# B171X.net
KiCad netlist of a schematic drawn in EAGLE
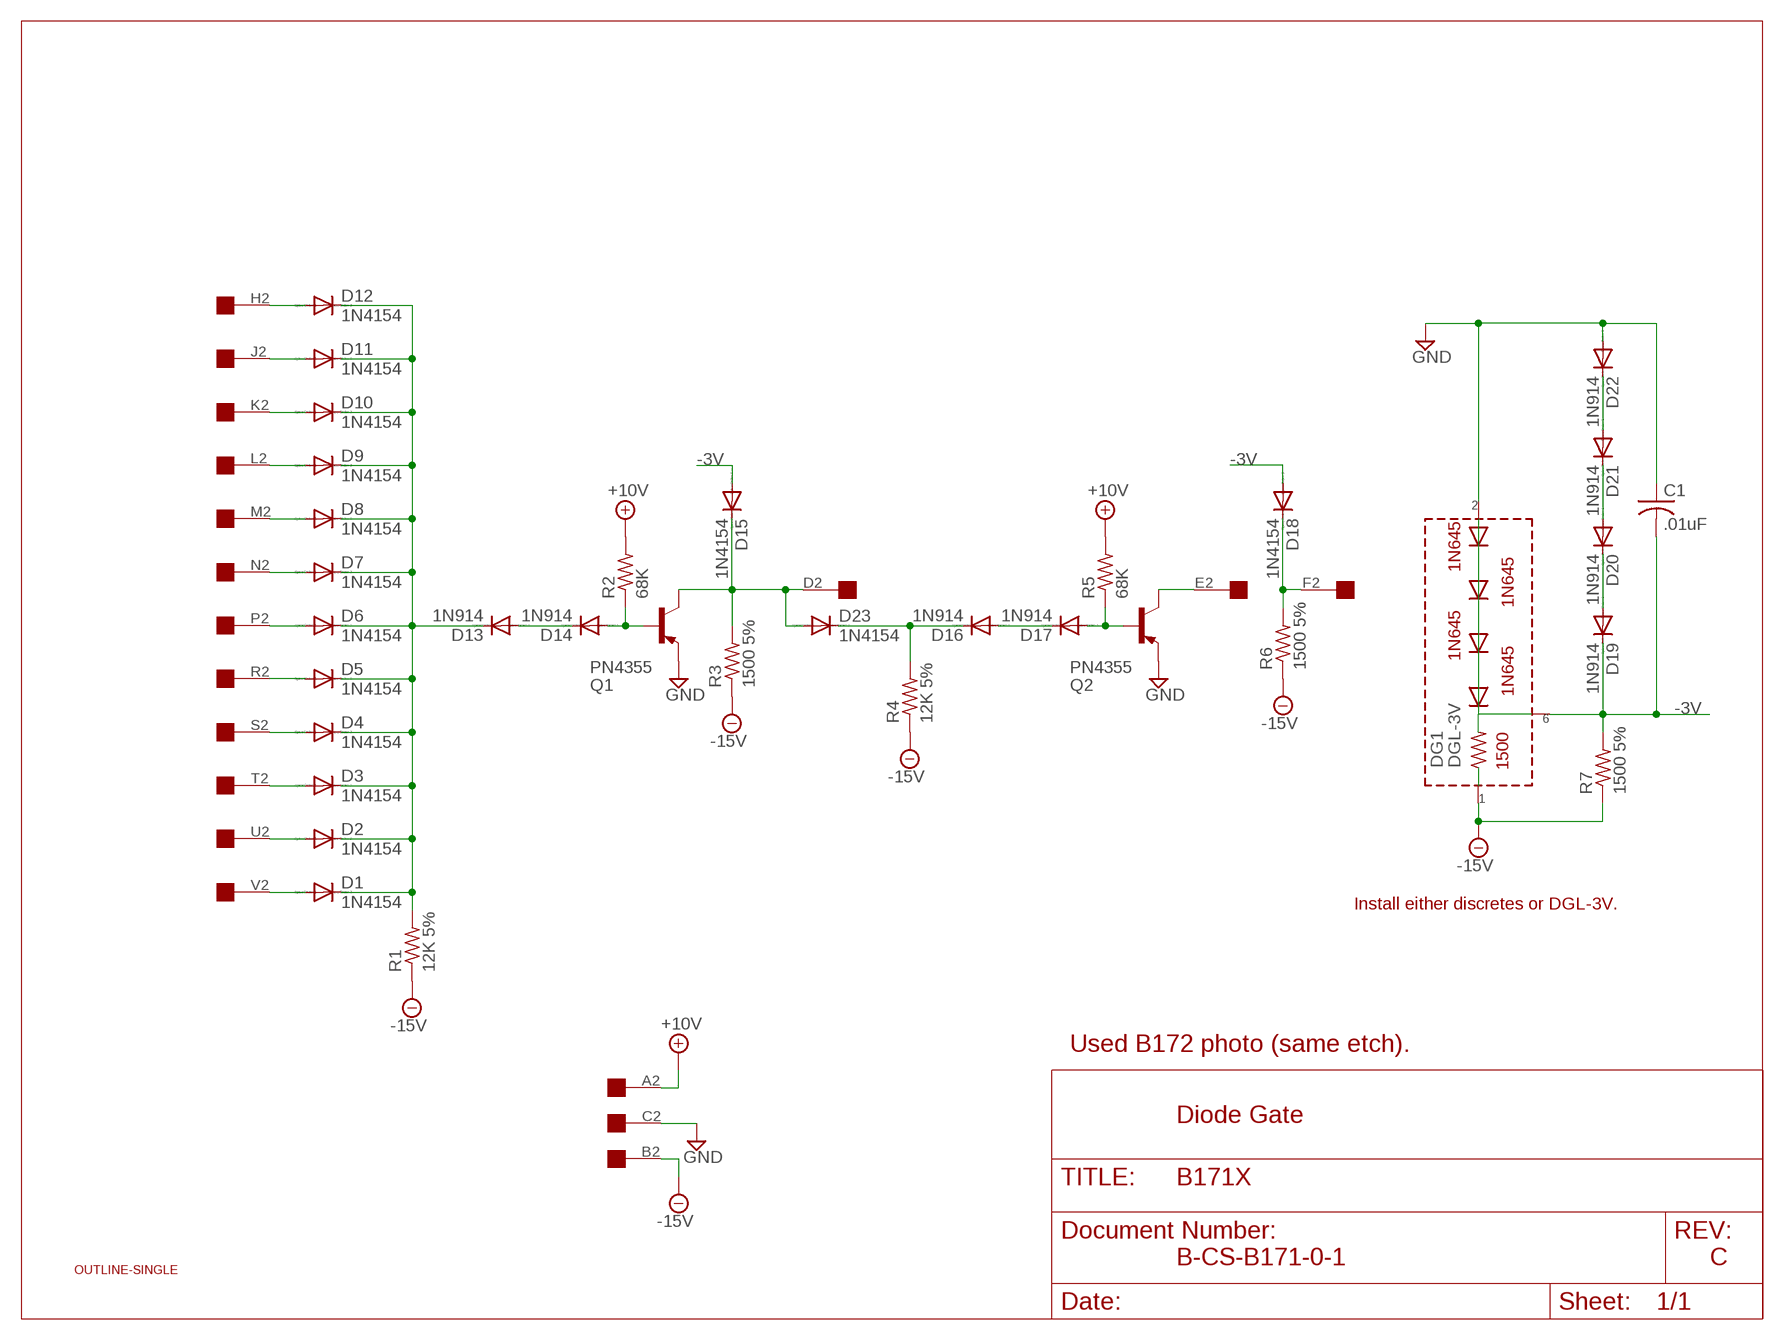
[diagram p0: schematic, sheet 1]

(export (version "E")
  (design (tool "Eeschema 10.0.6"))
  (components
    (comp (ref "C1")
      (value ".01uF")
      (footprint "eagle-import:C050-025X075")
      (libsource (lib "eagle-import") (part "C-US050-025X075"))
    )
    (comp (ref "D1")
      (value "1N4154")
      (footprint "eagle-import:DO35-10")
      (libsource (lib "eagle-import") (part "DIODE-DO35-10"))
    )
    (comp (ref "D2")
      (value "1N4154")
      (footprint "eagle-import:DO35-10")
      (libsource (lib "eagle-import") (part "DIODE-DO35-10"))
    )
    (comp (ref "D3")
      (value "1N4154")
      (footprint "eagle-import:DO35-10")
      (libsource (lib "eagle-import") (part "DIODE-DO35-10"))
    )
    (comp (ref "D4")
      (value "1N4154")
      (footprint "eagle-import:DO35-10")
      (libsource (lib "eagle-import") (part "DIODE-DO35-10"))
    )
    (comp (ref "D5")
      (value "1N4154")
      (footprint "eagle-import:DO35-10")
      (libsource (lib "eagle-import") (part "DIODE-DO35-10"))
    )
    (comp (ref "D6")
      (value "1N4154")
      (footprint "eagle-import:DO35-10")
      (libsource (lib "eagle-import") (part "DIODE-DO35-10"))
    )
    (comp (ref "D7")
      (value "1N4154")
      (footprint "eagle-import:DO35-10")
      (libsource (lib "eagle-import") (part "DIODE-DO35-10"))
    )
    (comp (ref "D8")
      (value "1N4154")
      (footprint "eagle-import:DO35-10")
      (libsource (lib "eagle-import") (part "DIODE-DO35-10"))
    )
    (comp (ref "D9")
      (value "1N4154")
      (footprint "eagle-import:DO35-10")
      (libsource (lib "eagle-import") (part "DIODE-DO35-10"))
    )
    (comp (ref "D10")
      (value "1N4154")
      (footprint "eagle-import:DO35-10")
      (libsource (lib "eagle-import") (part "DIODE-DO35-10"))
    )
    (comp (ref "D11")
      (value "1N4154")
      (footprint "eagle-import:DO35-10")
      (libsource (lib "eagle-import") (part "DIODE-DO35-10"))
    )
    (comp (ref "D12")
      (value "1N4154")
      (footprint "eagle-import:DO35-10")
      (libsource (lib "eagle-import") (part "DIODE-DO35-10"))
    )
    (comp (ref "D13")
      (value "1N914")
      (footprint "eagle-import:DO35-10")
      (libsource (lib "eagle-import") (part "DIODE-DO35-10"))
    )
    (comp (ref "D14")
      (value "1N914")
      (footprint "eagle-import:DO35-10")
      (libsource (lib "eagle-import") (part "DIODE-DO35-10"))
    )
    (comp (ref "D15")
      (value "1N4154")
      (footprint "eagle-import:DO35-10")
      (libsource (lib "eagle-import") (part "DIODE-DO35-10"))
    )
    (comp (ref "D16")
      (value "1N914")
      (footprint "eagle-import:DO35-10")
      (libsource (lib "eagle-import") (part "DIODE-DO35-10"))
    )
    (comp (ref "D17")
      (value "1N914")
      (footprint "eagle-import:DO35-10")
      (libsource (lib "eagle-import") (part "DIODE-DO35-10"))
    )
    (comp (ref "D18")
      (value "1N4154")
      (footprint "eagle-import:DO35-10")
      (libsource (lib "eagle-import") (part "DIODE-DO35-10"))
    )
    (comp (ref "D19")
      (value "1N914")
      (footprint "eagle-import:DO35-10")
      (libsource (lib "eagle-import") (part "DIODE-DO35-10"))
    )
    (comp (ref "D20")
      (value "1N914")
      (footprint "eagle-import:DO35-10")
      (libsource (lib "eagle-import") (part "DIODE-DO35-10"))
    )
    (comp (ref "D21")
      (value "1N914")
      (footprint "eagle-import:DO35-10")
      (libsource (lib "eagle-import") (part "DIODE-DO35-10"))
    )
    (comp (ref "D22")
      (value "1N914")
      (footprint "eagle-import:DO35-10")
      (libsource (lib "eagle-import") (part "DIODE-DO35-10"))
    )
    (comp (ref "D23")
      (value "1N4154")
      (footprint "eagle-import:DO35-10")
      (libsource (lib "eagle-import") (part "DIODE-DO35-10"))
    )
    (comp (ref "DG1")
      (value "DGL-3V")
      (footprint "eagle-import:DGL2")
      (libsource (lib "eagle-import") (part "DGL-3V"))
    )
    (comp (ref "Q1")
      (value "PN4355")
      (footprint "eagle-import:TO5")
      (libsource (lib "eagle-import") (part "-PNP-TO5"))
    )
    (comp (ref "Q2")
      (value "PN4355")
      (footprint "eagle-import:TO5")
      (libsource (lib "eagle-import") (part "-PNP-TO5"))
    )
    (comp (ref "R1")
      (value "12K 5%")
      (footprint "eagle-import:0207_10")
      (libsource (lib "eagle-import") (part "R-US_0207/10"))
    )
    (comp (ref "R2")
      (value "68K")
      (footprint "eagle-import:0207_10")
      (libsource (lib "eagle-import") (part "R-US_0207/10"))
    )
    (comp (ref "R3")
      (value "1500 5%")
      (footprint "eagle-import:0207_10")
      (libsource (lib "eagle-import") (part "R-US_0207/10"))
    )
    (comp (ref "R4")
      (value "12K 5%")
      (footprint "eagle-import:0207_10")
      (libsource (lib "eagle-import") (part "R-US_0207/10"))
    )
    (comp (ref "R5")
      (value "68K")
      (footprint "eagle-import:0207_10")
      (libsource (lib "eagle-import") (part "R-US_0207/10"))
    )
    (comp (ref "R6")
      (value "1500 5%")
      (footprint "eagle-import:0207_10")
      (libsource (lib "eagle-import") (part "R-US_0207/10"))
    )
    (comp (ref "R7")
      (value "1500 5%")
      (footprint "eagle-import:0207_10")
      (libsource (lib "eagle-import") (part "R-US_0207/10"))
    )
    (comp (ref "U$1")
      (value "OUTLINE-SINGLE")
      (footprint "eagle-import:SINGLE")
      (libsource (lib "eagle-import") (part "OUTLINE-SINGLE"))
    )
    (comp (ref "U$2")
      (value "EDGE-1")
      (footprint "eagle-import:EDGE-CON1")
      (libsource (lib "eagle-import") (part "EDGE-1"))
    )
  )
  (nets
    (net (code "1") (name "+10V") (class "Default")
      (node (ref "R2") (pin "2") (pinfunction "2_2") (pintype "passive"))
      (node (ref "R5") (pin "2") (pinfunction "2_2") (pintype "passive"))
      (node (ref "U$2") (pin "A2") (pinfunction "1_A2") (pintype "bidirectional"))
    )
    (net (code "2") (name "-15V") (class "Default")
      (node (ref "DG1") (pin "P$1") (pinfunction "1_P$1") (pintype "passive"))
      (node (ref "R1") (pin "1") (pinfunction "1_1") (pintype "passive"))
      (node (ref "R3") (pin "1") (pinfunction "1_1") (pintype "passive"))
      (node (ref "R4") (pin "1") (pinfunction "1_1") (pintype "passive"))
      (node (ref "R6") (pin "1") (pinfunction "1_1") (pintype "passive"))
      (node (ref "R7") (pin "1") (pinfunction "1_1") (pintype "passive"))
      (node (ref "U$2") (pin "B2") (pinfunction "1_B2") (pintype "bidirectional"))
    )
    (net (code "3") (name "/-3V") (class "Default")
      (node (ref "C1") (pin "2") (pinfunction "2_2") (pintype "passive"))
      (node (ref "D15") (pin "A") (pinfunction "A_A") (pintype "passive"))
      (node (ref "D18") (pin "A") (pinfunction "A_A") (pintype "passive"))
      (node (ref "D19") (pin "C") (pinfunction "C_C") (pintype "passive"))
      (node (ref "DG1") (pin "P$6") (pinfunction "6_P$6") (pintype "passive"))
      (node (ref "R7") (pin "2") (pinfunction "2_2") (pintype "passive"))
    )
    (net (code "4") (name "GND") (class "Default")
      (node (ref "C1") (pin "1") (pinfunction "1_1") (pintype "passive"))
      (node (ref "D22") (pin "A") (pinfunction "A_A") (pintype "passive"))
      (node (ref "DG1") (pin "P$2") (pinfunction "2_P$2") (pintype "passive"))
      (node (ref "Q1") (pin "1") (pinfunction "E_1") (pintype "passive"))
      (node (ref "Q2") (pin "1") (pinfunction "E_1") (pintype "passive"))
      (node (ref "U$2") (pin "C2") (pinfunction "1_C2") (pintype "bidirectional"))
    )
    (net (code "5") (name "Net-(D1-PadC)") (class "Default")
      (node (ref "D1") (pin "C") (pinfunction "C_C") (pintype "passive"))
      (node (ref "D10") (pin "C") (pinfunction "C_C") (pintype "passive"))
      (node (ref "D11") (pin "C") (pinfunction "C_C") (pintype "passive"))
      (node (ref "D12") (pin "C") (pinfunction "C_C") (pintype "passive"))
      (node (ref "D13") (pin "C") (pinfunction "C_C") (pintype "passive"))
      (node (ref "D2") (pin "C") (pinfunction "C_C") (pintype "passive"))
      (node (ref "D3") (pin "C") (pinfunction "C_C") (pintype "passive"))
      (node (ref "D4") (pin "C") (pinfunction "C_C") (pintype "passive"))
      (node (ref "D5") (pin "C") (pinfunction "C_C") (pintype "passive"))
      (node (ref "D6") (pin "C") (pinfunction "C_C") (pintype "passive"))
      (node (ref "D7") (pin "C") (pinfunction "C_C") (pintype "passive"))
      (node (ref "D8") (pin "C") (pinfunction "C_C") (pintype "passive"))
      (node (ref "D9") (pin "C") (pinfunction "C_C") (pintype "passive"))
      (node (ref "R1") (pin "2") (pinfunction "2_2") (pintype "passive"))
    )
    (net (code "6") (name "Net-(D13-PadA)") (class "Default")
      (node (ref "D13") (pin "A") (pinfunction "A_A") (pintype "passive"))
      (node (ref "D14") (pin "C") (pinfunction "C_C") (pintype "passive"))
    )
    (net (code "7") (name "Net-(D16-PadA)") (class "Default")
      (node (ref "D16") (pin "A") (pinfunction "A_A") (pintype "passive"))
      (node (ref "D17") (pin "C") (pinfunction "C_C") (pintype "passive"))
    )
    (net (code "8") (name "Net-(D16-PadC)") (class "Default")
      (node (ref "D16") (pin "C") (pinfunction "C_C") (pintype "passive"))
      (node (ref "D23") (pin "C") (pinfunction "C_C") (pintype "passive"))
      (node (ref "R4") (pin "2") (pinfunction "2_2") (pintype "passive"))
    )
    (net (code "9") (name "Net-(D19-PadA)") (class "Default")
      (node (ref "D19") (pin "A") (pinfunction "A_A") (pintype "passive"))
      (node (ref "D20") (pin "C") (pinfunction "C_C") (pintype "passive"))
    )
    (net (code "10") (name "Net-(D20-PadA)") (class "Default")
      (node (ref "D20") (pin "A") (pinfunction "A_A") (pintype "passive"))
      (node (ref "D21") (pin "C") (pinfunction "C_C") (pintype "passive"))
    )
    (net (code "11") (name "Net-(D21-PadA)") (class "Default")
      (node (ref "D21") (pin "A") (pinfunction "A_A") (pintype "passive"))
      (node (ref "D22") (pin "C") (pinfunction "C_C") (pintype "passive"))
    )
    (net (code "12") (name "Net-(Q1-B)") (class "Default")
      (node (ref "D14") (pin "A") (pinfunction "A_A") (pintype "passive"))
      (node (ref "Q1") (pin "2") (pinfunction "B_2") (pintype "passive"))
      (node (ref "R2") (pin "1") (pinfunction "1_1") (pintype "passive"))
    )
    (net (code "13") (name "Net-(Q1-C)") (class "Default")
      (node (ref "D15") (pin "C") (pinfunction "C_C") (pintype "passive"))
      (node (ref "D23") (pin "A") (pinfunction "A_A") (pintype "passive"))
      (node (ref "Q1") (pin "3") (pinfunction "C_3") (pintype "passive"))
      (node (ref "R3") (pin "2") (pinfunction "2_2") (pintype "passive"))
      (node (ref "U$2") (pin "D2") (pinfunction "1_D2") (pintype "bidirectional"))
    )
    (net (code "14") (name "Net-(Q2-B)") (class "Default")
      (node (ref "D17") (pin "A") (pinfunction "A_A") (pintype "passive"))
      (node (ref "Q2") (pin "2") (pinfunction "B_2") (pintype "passive"))
      (node (ref "R5") (pin "1") (pinfunction "1_1") (pintype "passive"))
    )
    (net (code "15") (name "Net-(Q2-C)") (class "Default")
      (node (ref "Q2") (pin "3") (pinfunction "C_3") (pintype "passive"))
      (node (ref "U$2") (pin "E2") (pinfunction "1_E2") (pintype "bidirectional"))
    )
    (net (code "16") (name "Net-(U$2F-1)") (class "Default")
      (node (ref "D18") (pin "C") (pinfunction "C_C") (pintype "passive"))
      (node (ref "R6") (pin "2") (pinfunction "2_2") (pintype "passive"))
      (node (ref "U$2") (pin "F2") (pinfunction "1_F2") (pintype "bidirectional"))
    )
    (net (code "17") (name "Net-(U$2G-1)") (class "Default")
      (node (ref "D12") (pin "A") (pinfunction "A_A") (pintype "passive"))
      (node (ref "U$2") (pin "H2") (pinfunction "1_H2") (pintype "bidirectional"))
    )
    (net (code "18") (name "Net-(U$2H-1)") (class "Default")
      (node (ref "D11") (pin "A") (pinfunction "A_A") (pintype "passive"))
      (node (ref "U$2") (pin "J2") (pinfunction "1_J2") (pintype "bidirectional"))
    )
    (net (code "19") (name "Net-(U$2I-1)") (class "Default")
      (node (ref "D10") (pin "A") (pinfunction "A_A") (pintype "passive"))
      (node (ref "U$2") (pin "K2") (pinfunction "1_K2") (pintype "bidirectional"))
    )
    (net (code "20") (name "Net-(U$2J-1)") (class "Default")
      (node (ref "D9") (pin "A") (pinfunction "A_A") (pintype "passive"))
      (node (ref "U$2") (pin "L2") (pinfunction "1_L2") (pintype "bidirectional"))
    )
    (net (code "21") (name "Net-(U$2K-1)") (class "Default")
      (node (ref "D8") (pin "A") (pinfunction "A_A") (pintype "passive"))
      (node (ref "U$2") (pin "M2") (pinfunction "1_M2") (pintype "bidirectional"))
    )
    (net (code "22") (name "Net-(U$2L-1)") (class "Default")
      (node (ref "D7") (pin "A") (pinfunction "A_A") (pintype "passive"))
      (node (ref "U$2") (pin "N2") (pinfunction "1_N2") (pintype "bidirectional"))
    )
    (net (code "23") (name "Net-(U$2M-1)") (class "Default")
      (node (ref "D6") (pin "A") (pinfunction "A_A") (pintype "passive"))
      (node (ref "U$2") (pin "P2") (pinfunction "1_P2") (pintype "bidirectional"))
    )
    (net (code "24") (name "Net-(U$2N-1)") (class "Default")
      (node (ref "D5") (pin "A") (pinfunction "A_A") (pintype "passive"))
      (node (ref "U$2") (pin "R2") (pinfunction "1_R2") (pintype "bidirectional"))
    )
    (net (code "25") (name "Net-(U$2O-1)") (class "Default")
      (node (ref "D4") (pin "A") (pinfunction "A_A") (pintype "passive"))
      (node (ref "U$2") (pin "S2") (pinfunction "1_S2") (pintype "bidirectional"))
    )
    (net (code "26") (name "Net-(U$2P-1)") (class "Default")
      (node (ref "D3") (pin "A") (pinfunction "A_A") (pintype "passive"))
      (node (ref "U$2") (pin "T2") (pinfunction "1_T2") (pintype "bidirectional"))
    )
    (net (code "27") (name "Net-(U$2Q-1)") (class "Default")
      (node (ref "D2") (pin "A") (pinfunction "A_A") (pintype "passive"))
      (node (ref "U$2") (pin "U2") (pinfunction "1_U2") (pintype "bidirectional"))
    )
    (net (code "28") (name "Net-(U$2R-1)") (class "Default")
      (node (ref "D1") (pin "A") (pinfunction "A_A") (pintype "passive"))
      (node (ref "U$2") (pin "V2") (pinfunction "1_V2") (pintype "bidirectional"))
    )
  )
)
